# RedFly-Shield_v11.net
KiCad netlist of a schematic drawn in EAGLE
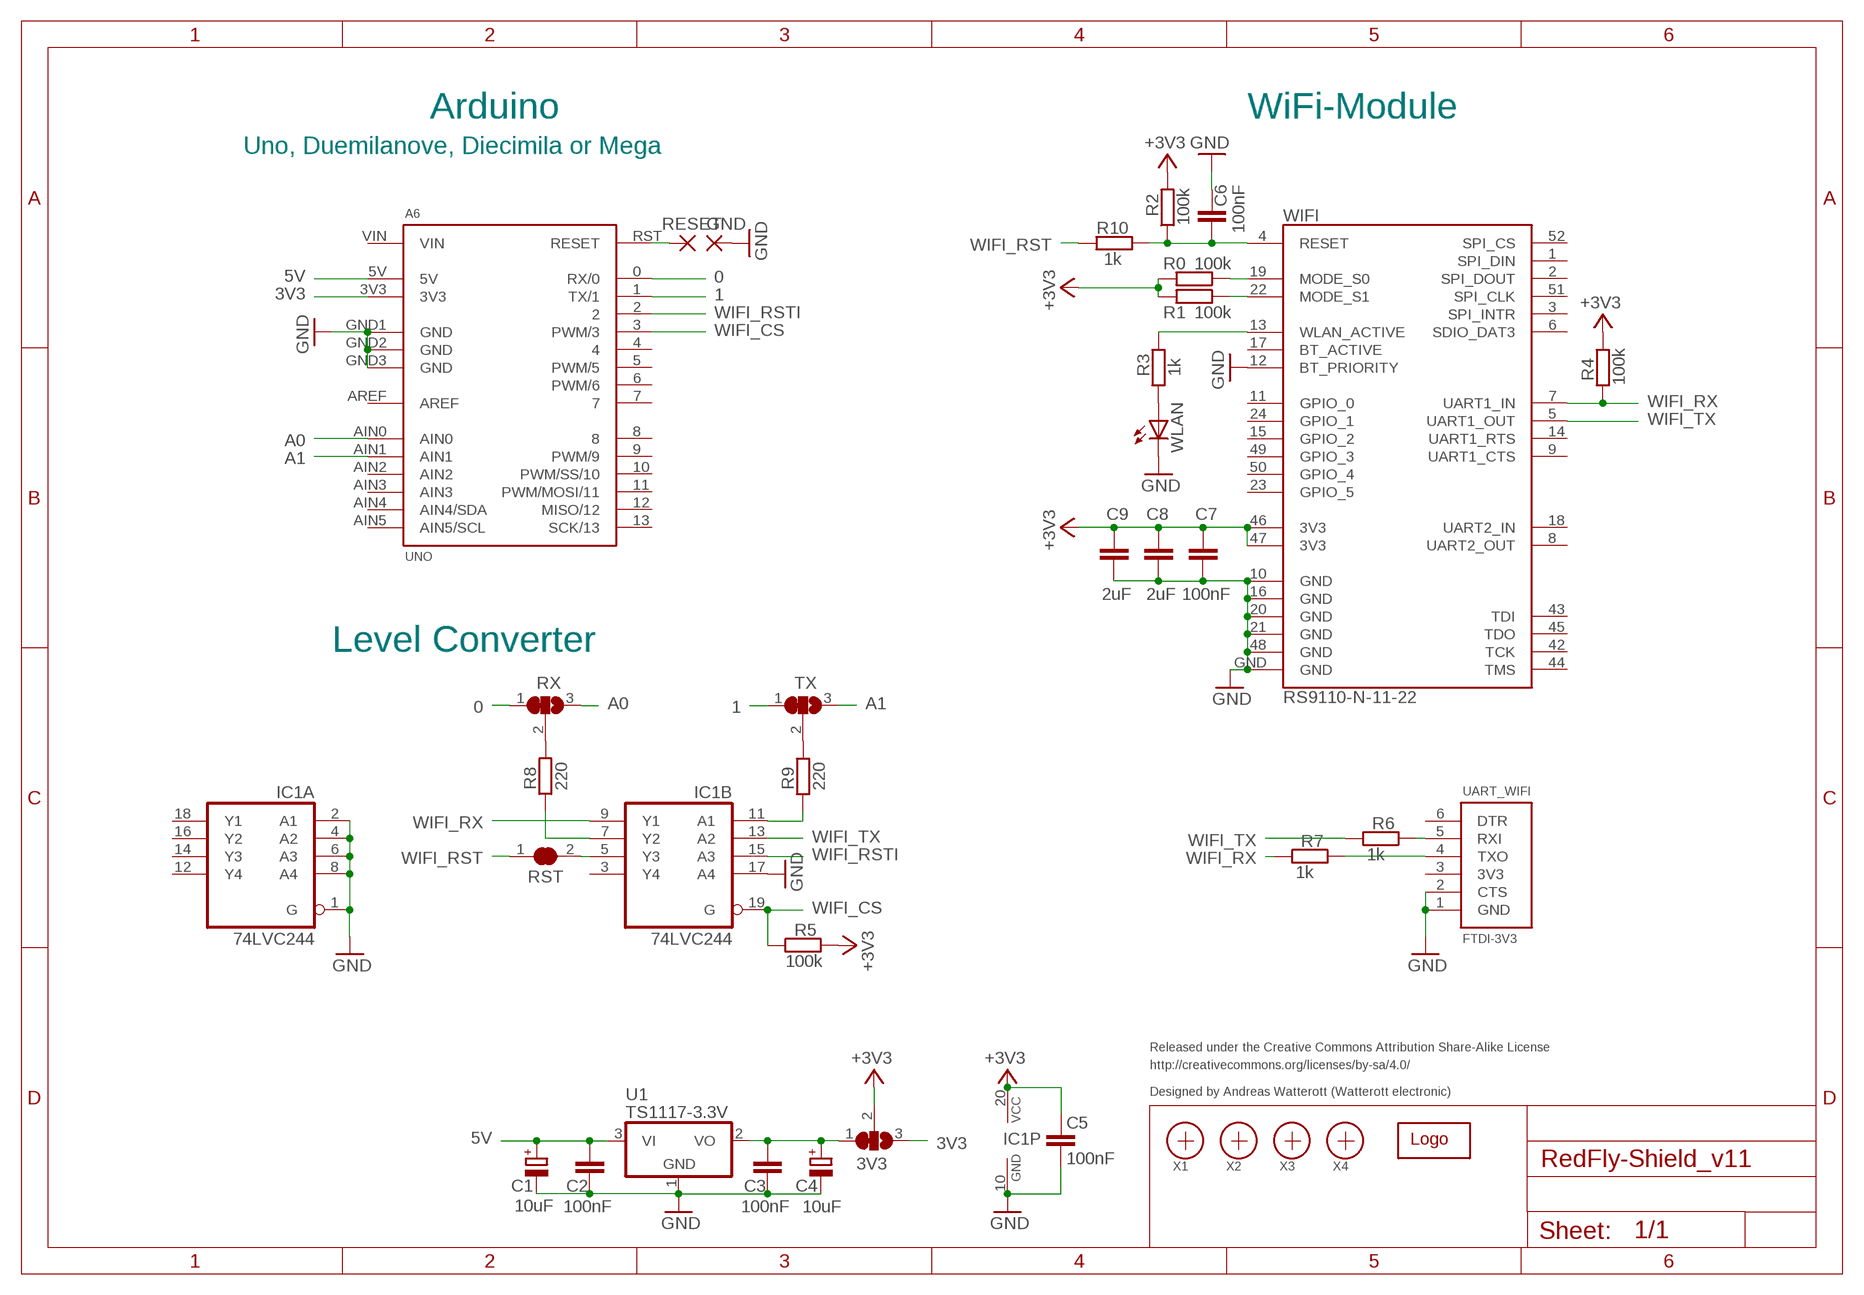
[diagram p0: schematic, sheet 1]

(export (version "E")
  (design (tool "Eeschema 10.0.6"))
  (components
    (comp (ref "3V3")
      (value "SJ2W")
      (footprint "eagle-import:SJ_2")
      (libsource (lib "eagle-import") (part "SJ2W"))
    )
    (comp (ref "A6")
      (value "UNO")
      (footprint "eagle-import:DUEMILANOVE")
      (libsource (lib "eagle-import") (part "DUEMILANOVE"))
    )
    (comp (ref "C1")
      (value "10uF")
      (footprint "eagle-import:153CLV-0505")
      (libsource (lib "eagle-import") (part "CPOL-EU153CLV-0505"))
    )
    (comp (ref "C2")
      (value "100nF")
      (footprint "eagle-import:C0603")
      (libsource (lib "eagle-import") (part "C-EUC0603"))
    )
    (comp (ref "C3")
      (value "100nF")
      (footprint "eagle-import:C0603")
      (libsource (lib "eagle-import") (part "C-EUC0603"))
    )
    (comp (ref "C4")
      (value "10uF")
      (footprint "eagle-import:153CLV-0505")
      (libsource (lib "eagle-import") (part "CPOL-EU153CLV-0505"))
    )
    (comp (ref "C5")
      (value "100nF")
      (footprint "eagle-import:C0603")
      (libsource (lib "eagle-import") (part "C-EUC0603"))
    )
    (comp (ref "C6")
      (value "100nF")
      (footprint "eagle-import:C0603")
      (libsource (lib "eagle-import") (part "C-EUC0603"))
    )
    (comp (ref "C7")
      (value "100nF")
      (footprint "eagle-import:C0603")
      (libsource (lib "eagle-import") (part "C-EUC0603"))
    )
    (comp (ref "C8")
      (value "2uF")
      (footprint "eagle-import:C0603")
      (libsource (lib "eagle-import") (part "C-EUC0603"))
    )
    (comp (ref "C9")
      (value "2uF")
      (footprint "eagle-import:C0603")
      (libsource (lib "eagle-import") (part "C-EUC0603"))
    )
    (comp (ref "GND")
      (value "SMD2")
      (footprint "eagle-import:SMD1,27-2,54")
      (libsource (lib "eagle-import") (part "SMD2"))
    )
    (comp (ref "IC1")
      (value "74LVC244")
      (footprint "eagle-import:SO20W")
      (libsource (lib "eagle-import") (part "74244DWHC"))
    )
    (comp (ref "R0")
      (value "100k")
      (footprint "eagle-import:R0603")
      (libsource (lib "eagle-import") (part "R-EU_R0603"))
    )
    (comp (ref "R1")
      (value "100k")
      (footprint "eagle-import:R0603")
      (libsource (lib "eagle-import") (part "R-EU_R0603"))
    )
    (comp (ref "R2")
      (value "100k")
      (footprint "eagle-import:R0603")
      (libsource (lib "eagle-import") (part "R-EU_R0603"))
    )
    (comp (ref "R3")
      (value "1k")
      (footprint "eagle-import:R0603")
      (libsource (lib "eagle-import") (part "R-EU_R0603"))
    )
    (comp (ref "R4")
      (value "100k")
      (footprint "eagle-import:R0603")
      (libsource (lib "eagle-import") (part "R-EU_R0603"))
    )
    (comp (ref "R5")
      (value "100k")
      (footprint "eagle-import:R0603")
      (libsource (lib "eagle-import") (part "R-EU_R0603"))
    )
    (comp (ref "R6")
      (value "1k")
      (footprint "eagle-import:R0603")
      (libsource (lib "eagle-import") (part "R-EU_R0603"))
    )
    (comp (ref "R7")
      (value "1k")
      (footprint "eagle-import:R0603")
      (libsource (lib "eagle-import") (part "R-EU_R0603"))
    )
    (comp (ref "R8")
      (value "220")
      (footprint "eagle-import:R0603")
      (libsource (lib "eagle-import") (part "R-EU_R0603"))
    )
    (comp (ref "R9")
      (value "220")
      (footprint "eagle-import:R0603")
      (libsource (lib "eagle-import") (part "R-EU_R0603"))
    )
    (comp (ref "R10")
      (value "1k")
      (footprint "eagle-import:R0603")
      (libsource (lib "eagle-import") (part "R-EU_R0603"))
    )
    (comp (ref "RESET")
      (value "SMD2")
      (footprint "eagle-import:SMD1,27-2,54")
      (libsource (lib "eagle-import") (part "SMD2"))
    )
    (comp (ref "RST") (value "SJ") (footprint "eagle-import:SJ") (libsource (lib "eagle-import") (part "SJ")))
    (comp (ref "RX")
      (value "SJ2W")
      (footprint "eagle-import:SJ_2")
      (libsource (lib "eagle-import") (part "SJ2W"))
    )
    (comp (ref "TX")
      (value "SJ2W")
      (footprint "eagle-import:SJ_2")
      (libsource (lib "eagle-import") (part "SJ2W"))
    )
    (comp (ref "U$1")
      (value "WE-LOGO")
      (footprint "eagle-import:WE-LOGO")
      (libsource (lib "eagle-import") (part "WE-LOGO"))
    )
    (comp (ref "U1")
      (value "TS1117-3.3V")
      (footprint "eagle-import:SOT223")
      (libsource (lib "eagle-import") (part "TS1117"))
    )
    (comp (ref "UART_WIFI")
      (value "FTDI-3V3")
      (footprint "eagle-import:FTDI")
      (libsource (lib "eagle-import") (part "FTDI"))
    )
    (comp (ref "WIFI")
      (value "RS9110-N-11-22")
      (footprint "eagle-import:RS9110-N-11-21")
      (libsource (lib "eagle-import") (part "RS9110-N-11-21"))
    )
    (comp (ref "WLAN")
      (value "LEDCHIPLED_0805")
      (footprint "eagle-import:CHIPLED_0805")
      (libsource (lib "eagle-import") (part "LEDCHIPLED_0805"))
    )
    (comp (ref "X1")
      (value "PASSER")
      (footprint "eagle-import:PASSER")
      (libsource (lib "eagle-import") (part "PASSER"))
    )
    (comp (ref "X2")
      (value "PASSER")
      (footprint "eagle-import:PASSER")
      (libsource (lib "eagle-import") (part "PASSER"))
    )
    (comp (ref "X3")
      (value "PASSER")
      (footprint "eagle-import:PASSER")
      (libsource (lib "eagle-import") (part "PASSER"))
    )
    (comp (ref "X4")
      (value "PASSER")
      (footprint "eagle-import:PASSER")
      (libsource (lib "eagle-import") (part "PASSER"))
    )
  )
  (nets
    (net (code "1") (name "+3V3") (class "Default")
      (node (ref "3V3") (pin "2") (pinfunction "2_2") (pintype "passive"))
      (node (ref "C5") (pin "1") (pinfunction "1_1") (pintype "passive"))
      (node (ref "C7") (pin "1") (pinfunction "1_1") (pintype "passive"))
      (node (ref "C8") (pin "1") (pinfunction "1_1") (pintype "passive"))
      (node (ref "C9") (pin "1") (pinfunction "1_1") (pintype "passive"))
      (node (ref "IC1") (pin "20") (pinfunction "VCC_20") (pintype "power_in"))
      (node (ref "R0") (pin "2") (pinfunction "2_2") (pintype "passive"))
      (node (ref "R1") (pin "2") (pinfunction "2_2") (pintype "passive"))
      (node (ref "R2") (pin "2") (pinfunction "2_2") (pintype "passive"))
      (node (ref "R4") (pin "1") (pinfunction "1_1") (pintype "passive"))
      (node (ref "R5") (pin "2") (pinfunction "2_2") (pintype "passive"))
      (node (ref "WIFI") (pin "46") (pinfunction "3V3_46") (pintype "power_in"))
      (node (ref "WIFI") (pin "47") (pinfunction "3V3_47") (pintype "power_in"))
    )
    (net (code "2") (name "/0") (class "Default")
      (node (ref "A6") (pin "0") (pinfunction "RX/0_0") (pintype "bidirectional"))
      (node (ref "RX") (pin "1") (pinfunction "1_1") (pintype "passive"))
    )
    (net (code "3") (name "/1") (class "Default")
      (node (ref "A6") (pin "1") (pinfunction "TX/1_1") (pintype "bidirectional"))
      (node (ref "TX") (pin "1") (pinfunction "1_1") (pintype "passive"))
    )
    (net (code "4") (name "/3V3") (class "Default")
      (node (ref "3V3") (pin "3") (pinfunction "3_3") (pintype "passive"))
      (node (ref "A6") (pin "3V3") (pinfunction "3V3_3V3") (pintype "power_in"))
    )
    (net (code "5") (name "/5V") (class "Default")
      (node (ref "A6") (pin "5V") (pinfunction "5V_5V") (pintype "power_in"))
      (node (ref "C1") (pin "+") (pinfunction "+_+") (pintype "passive"))
      (node (ref "C2") (pin "1") (pinfunction "1_1") (pintype "passive"))
      (node (ref "U1") (pin "3") (pinfunction "VI_3") (pintype "input"))
    )
    (net (code "6") (name "/A0") (class "Default")
      (node (ref "A6") (pin "AIN0") (pinfunction "AIN0_AIN0") (pintype "bidirectional"))
      (node (ref "RX") (pin "3") (pinfunction "3_3") (pintype "passive"))
    )
    (net (code "7") (name "/A1") (class "Default")
      (node (ref "A6") (pin "AIN1") (pinfunction "AIN1_AIN1") (pintype "bidirectional"))
      (node (ref "TX") (pin "3") (pinfunction "3_3") (pintype "passive"))
    )
    (net (code "8") (name "/AREF") (class "Default")
      (node (ref "A6") (pin "AREF") (pinfunction "AREF_AREF") (pintype "power_in"))
    )
    (net (code "9") (name "/VIN") (class "Default")
      (node (ref "A6") (pin "VIN") (pinfunction "VIN_VIN") (pintype "power_in"))
    )
    (net (code "10") (name "/WIFI_CS") (class "Default")
      (node (ref "A6") (pin "3") (pinfunction "PWM/3_3") (pintype "bidirectional"))
      (node (ref "IC1") (pin "19") (pinfunction "G_19") (pintype "input"))
      (node (ref "R5") (pin "1") (pinfunction "1_1") (pintype "passive"))
    )
    (net (code "11") (name "/WIFI_RST") (class "Default")
      (node (ref "R10") (pin "2") (pinfunction "2_2") (pintype "passive"))
      (node (ref "RST") (pin "1") (pinfunction "1_1") (pintype "passive"))
    )
    (net (code "12") (name "/WIFI_RSTI") (class "Default")
      (node (ref "A6") (pin "2") (pinfunction "2_2") (pintype "bidirectional"))
      (node (ref "IC1") (pin "15") (pinfunction "A3_15") (pintype "input"))
    )
    (net (code "13") (name "/WIFI_RX") (class "Default")
      (node (ref "IC1") (pin "9") (pinfunction "Y1_9") (pintype "tri_state"))
      (node (ref "R4") (pin "2") (pinfunction "2_2") (pintype "passive"))
      (node (ref "R7") (pin "2") (pinfunction "2_2") (pintype "passive"))
      (node (ref "WIFI") (pin "7") (pinfunction "UART1_IN_7") (pintype "bidirectional"))
    )
    (net (code "14") (name "/WIFI_TX") (class "Default")
      (node (ref "IC1") (pin "13") (pinfunction "A2_13") (pintype "input"))
      (node (ref "R6") (pin "2") (pinfunction "2_2") (pintype "passive"))
      (node (ref "WIFI") (pin "5") (pinfunction "UART1_OUT_5") (pintype "bidirectional"))
    )
    (net (code "15") (name "GND") (class "Default")
      (node (ref "A6") (pin "GND1") (pinfunction "GND_GND1") (pintype "power_in"))
      (node (ref "A6") (pin "GND2") (pinfunction "GND_GND2") (pintype "power_in"))
      (node (ref "A6") (pin "GND3") (pinfunction "GND_GND3") (pintype "power_in"))
      (node (ref "C1") (pin "-") (pinfunction "-_-") (pintype "passive"))
      (node (ref "C2") (pin "2") (pinfunction "2_2") (pintype "passive"))
      (node (ref "C3") (pin "2") (pinfunction "2_2") (pintype "passive"))
      (node (ref "C4") (pin "-") (pinfunction "-_-") (pintype "passive"))
      (node (ref "C5") (pin "2") (pinfunction "2_2") (pintype "passive"))
      (node (ref "C6") (pin "1") (pinfunction "1_1") (pintype "passive"))
      (node (ref "C7") (pin "2") (pinfunction "2_2") (pintype "passive"))
      (node (ref "C8") (pin "2") (pinfunction "2_2") (pintype "passive"))
      (node (ref "C9") (pin "2") (pinfunction "2_2") (pintype "passive"))
      (node (ref "GND") (pin "1") (pinfunction "P_1") (pintype "passive"))
      (node (ref "IC1") (pin "1") (pinfunction "G_1") (pintype "input"))
      (node (ref "IC1") (pin "10") (pinfunction "GND_10") (pintype "power_in"))
      (node (ref "IC1") (pin "17") (pinfunction "A4_17") (pintype "input"))
      (node (ref "IC1") (pin "2") (pinfunction "A1_2") (pintype "input"))
      (node (ref "IC1") (pin "4") (pinfunction "A2_4") (pintype "input"))
      (node (ref "IC1") (pin "6") (pinfunction "A3_6") (pintype "input"))
      (node (ref "IC1") (pin "8") (pinfunction "A4_8") (pintype "input"))
      (node (ref "U1") (pin "1") (pinfunction "GND_1") (pintype "passive"))
      (node (ref "UART_WIFI") (pin "1") (pinfunction "GND_1") (pintype "bidirectional"))
      (node (ref "UART_WIFI") (pin "2") (pinfunction "CTS_2") (pintype "bidirectional"))
      (node (ref "WIFI") (pin "10") (pinfunction "GND_10") (pintype "power_in"))
      (node (ref "WIFI") (pin "12") (pinfunction "BT_PRIORITY_12") (pintype "bidirectional"))
      (node (ref "WIFI") (pin "16") (pinfunction "GND_16") (pintype "power_in"))
      (node (ref "WIFI") (pin "20") (pinfunction "GND_20") (pintype "power_in"))
      (node (ref "WIFI") (pin "21") (pinfunction "GND_21") (pintype "power_in"))
      (node (ref "WIFI") (pin "48") (pinfunction "GND_48") (pintype "power_in"))
      (node (ref "WIFI") (pin "GND") (pinfunction "GND_GND") (pintype "power_in"))
      (node (ref "WLAN") (pin "C") (pinfunction "C_C") (pintype "passive"))
    )
    (net (code "16") (name "Net-(A6-RESET)") (class "Default")
      (node (ref "A6") (pin "RST") (pinfunction "RESET_RST") (pintype "bidirectional"))
      (node (ref "RESET") (pin "1") (pinfunction "P_1") (pintype "passive"))
    )
    (net (code "17") (name "Net-(IC1B-A1)") (class "Default")
      (node (ref "IC1") (pin "11") (pinfunction "A1_11") (pintype "input"))
      (node (ref "R9") (pin "2") (pinfunction "2_2") (pintype "passive"))
    )
    (net (code "18") (name "Net-(IC1B-Y2)") (class "Default")
      (node (ref "IC1") (pin "7") (pinfunction "Y2_7") (pintype "tri_state"))
      (node (ref "R8") (pin "1") (pinfunction "1_1") (pintype "passive"))
    )
    (net (code "19") (name "Net-(IC1B-Y3)") (class "Default")
      (node (ref "IC1") (pin "5") (pinfunction "Y3_5") (pintype "tri_state"))
      (node (ref "RST") (pin "2") (pinfunction "2_2") (pintype "passive"))
    )
    (net (code "20") (name "Net-(R3-Pad2)") (class "Default")
      (node (ref "R3") (pin "2") (pinfunction "2_2") (pintype "passive"))
      (node (ref "WLAN") (pin "A") (pinfunction "A_A") (pintype "passive"))
    )
    (net (code "21") (name "Net-(R8-Pad2)") (class "Default")
      (node (ref "R8") (pin "2") (pinfunction "2_2") (pintype "passive"))
      (node (ref "RX") (pin "2") (pinfunction "2_2") (pintype "passive"))
    )
    (net (code "22") (name "Net-(R9-Pad1)") (class "Default")
      (node (ref "R9") (pin "1") (pinfunction "1_1") (pintype "passive"))
      (node (ref "TX") (pin "2") (pinfunction "2_2") (pintype "passive"))
    )
    (net (code "23") (name "Net-(U1-VO)") (class "Default")
      (node (ref "3V3") (pin "1") (pinfunction "1_1") (pintype "passive"))
      (node (ref "C3") (pin "1") (pinfunction "1_1") (pintype "passive"))
      (node (ref "C4") (pin "+") (pinfunction "+_+") (pintype "passive"))
      (node (ref "U1") (pin "2") (pinfunction "VO_2") (pintype "passive"))
    )
    (net (code "24") (name "Net-(UART_WIFI-RXI)") (class "Default")
      (node (ref "R6") (pin "1") (pinfunction "1_1") (pintype "passive"))
      (node (ref "UART_WIFI") (pin "5") (pinfunction "RXI_5") (pintype "bidirectional"))
    )
    (net (code "25") (name "Net-(UART_WIFI-TXO)") (class "Default")
      (node (ref "R7") (pin "1") (pinfunction "1_1") (pintype "passive"))
      (node (ref "UART_WIFI") (pin "4") (pinfunction "TXO_4") (pintype "bidirectional"))
    )
    (net (code "26") (name "Net-(WIFI-MODE_S0)") (class "Default")
      (node (ref "R0") (pin "1") (pinfunction "1_1") (pintype "passive"))
      (node (ref "WIFI") (pin "19") (pinfunction "MODE_S0_19") (pintype "bidirectional"))
    )
    (net (code "27") (name "Net-(WIFI-MODE_S1)") (class "Default")
      (node (ref "R1") (pin "1") (pinfunction "1_1") (pintype "passive"))
      (node (ref "WIFI") (pin "22") (pinfunction "MODE_S1_22") (pintype "bidirectional"))
    )
    (net (code "28") (name "Net-(WIFI-RESET)") (class "Default")
      (node (ref "C6") (pin "2") (pinfunction "2_2") (pintype "passive"))
      (node (ref "R10") (pin "1") (pinfunction "1_1") (pintype "passive"))
      (node (ref "R2") (pin "1") (pinfunction "1_1") (pintype "passive"))
      (node (ref "WIFI") (pin "4") (pinfunction "RESET_4") (pintype "bidirectional"))
    )
    (net (code "29") (name "Net-(WIFI-WLAN_ACTIVE)") (class "Default")
      (node (ref "R3") (pin "1") (pinfunction "1_1") (pintype "passive"))
      (node (ref "WIFI") (pin "13") (pinfunction "WLAN_ACTIVE_13") (pintype "bidirectional"))
    )
    (net (code "30") (name "unconnected-(A6-AIN4{slash}SDA-PadAIN4)") (class "Default")
      (node (ref "A6") (pin "AIN4") (pinfunction "AIN4/SDA_AIN4") (pintype "bidirectional"))
    )
    (net (code "31") (name "unconnected-(A6-AIN5{slash}SCL-PadAIN5)") (class "Default")
      (node (ref "A6") (pin "AIN5") (pinfunction "AIN5/SCL_AIN5") (pintype "bidirectional"))
    )
    (net (code "32") (name "unconnected-(A6-MISO{slash}12-Pad12)") (class "Default")
      (node (ref "A6") (pin "12") (pinfunction "MISO/12_12") (pintype "bidirectional"))
    )
    (net (code "33") (name "unconnected-(A6-PWM{slash}5-Pad5)") (class "Default")
      (node (ref "A6") (pin "5") (pinfunction "PWM/5_5") (pintype "bidirectional"))
    )
    (net (code "34") (name "unconnected-(A6-PWM{slash}6-Pad6)") (class "Default")
      (node (ref "A6") (pin "6") (pinfunction "PWM/6_6") (pintype "bidirectional"))
    )
    (net (code "35") (name "unconnected-(A6-PWM{slash}9-Pad9)") (class "Default")
      (node (ref "A6") (pin "9") (pinfunction "PWM/9_9") (pintype "bidirectional"))
    )
    (net (code "36") (name "unconnected-(A6-PWM{slash}MOSI{slash}11-Pad11)") (class "Default")
      (node (ref "A6") (pin "11") (pinfunction "PWM/MOSI/11_11") (pintype "bidirectional"))
    )
    (net (code "37") (name "unconnected-(A6-PWM{slash}SS{slash}10-Pad10)") (class "Default")
      (node (ref "A6") (pin "10") (pinfunction "PWM/SS/10_10") (pintype "bidirectional"))
    )
    (net (code "38") (name "unconnected-(A6-Pad4)") (class "Default")
      (node (ref "A6") (pin "4") (pinfunction "4_4") (pintype "bidirectional"))
    )
    (net (code "39") (name "unconnected-(A6-Pad7)") (class "Default")
      (node (ref "A6") (pin "7") (pinfunction "7_7") (pintype "bidirectional"))
    )
    (net (code "40") (name "unconnected-(A6-Pad8)") (class "Default")
      (node (ref "A6") (pin "8") (pinfunction "8_8") (pintype "bidirectional"))
    )
    (net (code "41") (name "unconnected-(A6-PadAIN2)") (class "Default")
      (node (ref "A6") (pin "AIN2") (pinfunction "AIN2_AIN2") (pintype "bidirectional"))
    )
    (net (code "42") (name "unconnected-(A6-PadAIN3)") (class "Default")
      (node (ref "A6") (pin "AIN3") (pinfunction "AIN3_AIN3") (pintype "bidirectional"))
    )
    (net (code "43") (name "unconnected-(A6-SCK{slash}13-Pad13)") (class "Default")
      (node (ref "A6") (pin "13") (pinfunction "SCK/13_13") (pintype "bidirectional"))
    )
    (net (code "44") (name "unconnected-(IC1A-Y1-Pad18)") (class "Default")
      (node (ref "IC1") (pin "18") (pinfunction "Y1_18") (pintype "tri_state"))
    )
    (net (code "45") (name "unconnected-(IC1A-Y2-Pad16)") (class "Default")
      (node (ref "IC1") (pin "16") (pinfunction "Y2_16") (pintype "tri_state"))
    )
    (net (code "46") (name "unconnected-(IC1A-Y3-Pad14)") (class "Default")
      (node (ref "IC1") (pin "14") (pinfunction "Y3_14") (pintype "tri_state"))
    )
    (net (code "47") (name "unconnected-(IC1A-Y4-Pad12)") (class "Default")
      (node (ref "IC1") (pin "12") (pinfunction "Y4_12") (pintype "tri_state"))
    )
    (net (code "48") (name "unconnected-(IC1B-Y4-Pad3)") (class "Default")
      (node (ref "IC1") (pin "3") (pinfunction "Y4_3") (pintype "tri_state"))
    )
    (net (code "49") (name "unconnected-(UART_WIFI-3V3-Pad3)") (class "Default")
      (node (ref "UART_WIFI") (pin "3") (pinfunction "3V3_3") (pintype "bidirectional"))
    )
    (net (code "50") (name "unconnected-(UART_WIFI-DTR-Pad6)") (class "Default")
      (node (ref "UART_WIFI") (pin "6") (pinfunction "DTR_6") (pintype "bidirectional"))
    )
    (net (code "51") (name "unconnected-(WIFI-BT_ACTIVE-Pad17)") (class "Default")
      (node (ref "WIFI") (pin "17") (pinfunction "BT_ACTIVE_17") (pintype "bidirectional"))
    )
    (net (code "52") (name "unconnected-(WIFI-GPIO_0-Pad11)") (class "Default")
      (node (ref "WIFI") (pin "11") (pinfunction "GPIO_0_11") (pintype "bidirectional"))
    )
    (net (code "53") (name "unconnected-(WIFI-GPIO_1-Pad24)") (class "Default")
      (node (ref "WIFI") (pin "24") (pinfunction "GPIO_1_24") (pintype "bidirectional"))
    )
    (net (code "54") (name "unconnected-(WIFI-GPIO_2-Pad15)") (class "Default")
      (node (ref "WIFI") (pin "15") (pinfunction "GPIO_2_15") (pintype "bidirectional"))
    )
    (net (code "55") (name "unconnected-(WIFI-GPIO_3-Pad49)") (class "Default")
      (node (ref "WIFI") (pin "49") (pinfunction "GPIO_3_49") (pintype "bidirectional"))
    )
    (net (code "56") (name "unconnected-(WIFI-GPIO_4-Pad50)") (class "Default")
      (node (ref "WIFI") (pin "50") (pinfunction "GPIO_4_50") (pintype "bidirectional"))
    )
    (net (code "57") (name "unconnected-(WIFI-GPIO_5-Pad23)") (class "Default")
      (node (ref "WIFI") (pin "23") (pinfunction "GPIO_5_23") (pintype "bidirectional"))
    )
    (net (code "58") (name "unconnected-(WIFI-SDIO_DAT3-Pad6)") (class "Default")
      (node (ref "WIFI") (pin "6") (pinfunction "SDIO_DAT3_6") (pintype "bidirectional"))
    )
    (net (code "59") (name "unconnected-(WIFI-SPI_CLK-Pad51)") (class "Default")
      (node (ref "WIFI") (pin "51") (pinfunction "SPI_CLK_51") (pintype "bidirectional"))
    )
    (net (code "60") (name "unconnected-(WIFI-SPI_CS-Pad52)") (class "Default")
      (node (ref "WIFI") (pin "52") (pinfunction "SPI_CS_52") (pintype "bidirectional"))
    )
    (net (code "61") (name "unconnected-(WIFI-SPI_DIN-Pad1)") (class "Default")
      (node (ref "WIFI") (pin "1") (pinfunction "SPI_DIN_1") (pintype "bidirectional"))
    )
    (net (code "62") (name "unconnected-(WIFI-SPI_DOUT-Pad2)") (class "Default")
      (node (ref "WIFI") (pin "2") (pinfunction "SPI_DOUT_2") (pintype "bidirectional"))
    )
    (net (code "63") (name "unconnected-(WIFI-SPI_INTR-Pad3)") (class "Default")
      (node (ref "WIFI") (pin "3") (pinfunction "SPI_INTR_3") (pintype "bidirectional"))
    )
    (net (code "64") (name "unconnected-(WIFI-TCK-Pad42)") (class "Default")
      (node (ref "WIFI") (pin "42") (pinfunction "TCK_42") (pintype "bidirectional"))
    )
    (net (code "65") (name "unconnected-(WIFI-TDI-Pad43)") (class "Default")
      (node (ref "WIFI") (pin "43") (pinfunction "TDI_43") (pintype "bidirectional"))
    )
    (net (code "66") (name "unconnected-(WIFI-TDO-Pad45)") (class "Default")
      (node (ref "WIFI") (pin "45") (pinfunction "TDO_45") (pintype "bidirectional"))
    )
    (net (code "67") (name "unconnected-(WIFI-TMS-Pad44)") (class "Default")
      (node (ref "WIFI") (pin "44") (pinfunction "TMS_44") (pintype "bidirectional"))
    )
    (net (code "68") (name "unconnected-(WIFI-UART1_CTS-Pad9)") (class "Default")
      (node (ref "WIFI") (pin "9") (pinfunction "UART1_CTS_9") (pintype "bidirectional"))
    )
    (net (code "69") (name "unconnected-(WIFI-UART1_RTS-Pad14)") (class "Default")
      (node (ref "WIFI") (pin "14") (pinfunction "UART1_RTS_14") (pintype "bidirectional"))
    )
    (net (code "70") (name "unconnected-(WIFI-UART2_IN-Pad18)") (class "Default")
      (node (ref "WIFI") (pin "18") (pinfunction "UART2_IN_18") (pintype "bidirectional"))
    )
    (net (code "71") (name "unconnected-(WIFI-UART2_OUT-Pad8)") (class "Default")
      (node (ref "WIFI") (pin "8") (pinfunction "UART2_OUT_8") (pintype "bidirectional"))
    )
  )
)
